# 01_-_POWER_SUPPLY.net
KiCad netlist of a schematic drawn in Altium Designer
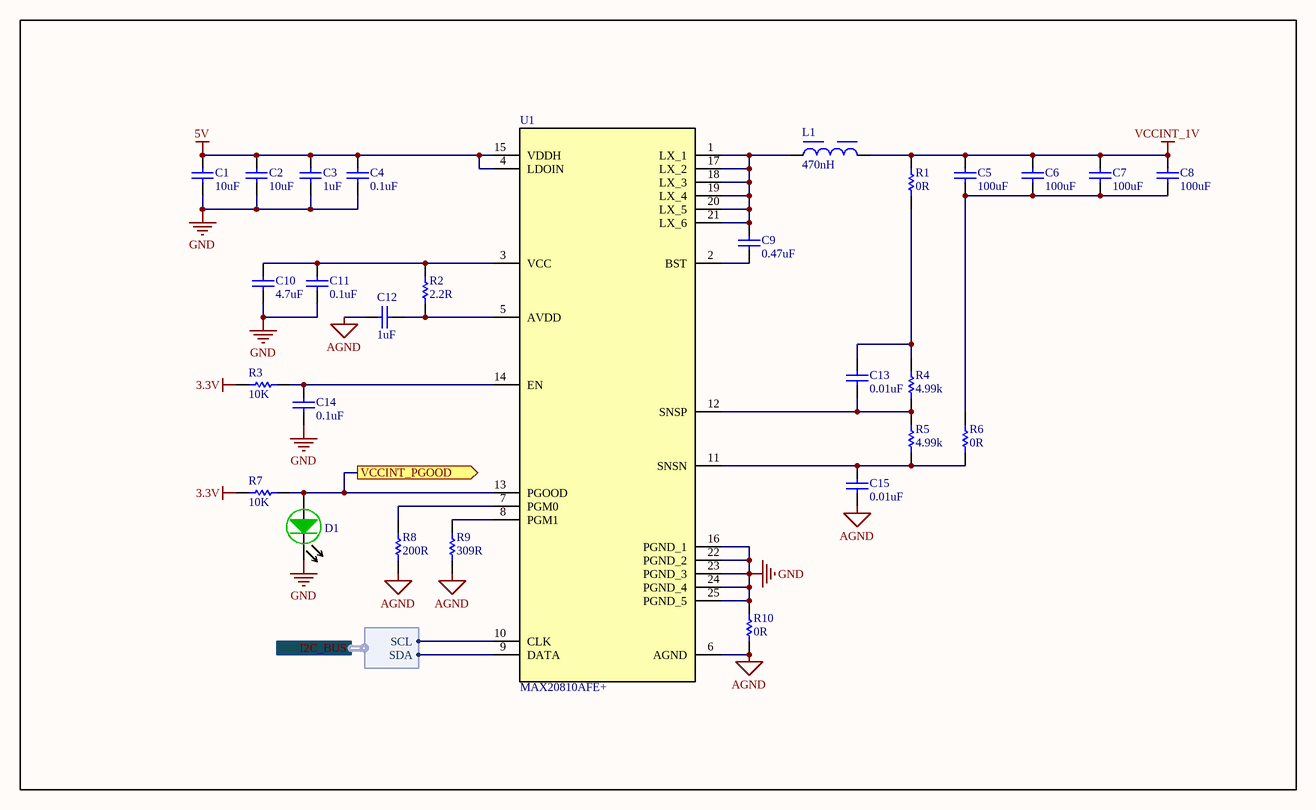
[diagram p0: 01 - POWER SUPPLY.SchDoc]

(export (version "E")
  (design (tool "Eeschema 10.0.6"))
  (components
    (comp (ref "C1")
      (value "10uF")
      (footprint "0603-C-R")
      (description "CAP SMD 0603 MLCC GERAL 10uF 10V ±10% X7R PN: GRM188Z71A106KA73D")
      (fields (field (name "VOLTAGE") "10V") (field (name "TOLERANCE") "10%"))
      (libsource (lib "Schlib") (part "CAP SMD 0603 10uF 10V ±10%"))
    )
    (comp (ref "C2")
      (value "10uF")
      (footprint "0603-C-R")
      (description "CAP SMD 0603 MLCC GERAL 10uF 10V ±10% X7R PN: GRM188Z71A106KA73D")
      (fields (field (name "VOLTAGE") "10V") (field (name "TOLERANCE") "10%"))
      (libsource (lib "Schlib") (part "CAP SMD 0603 10uF 10V ±10%"))
    )
    (comp (ref "C3")
      (value "1uF")
      (footprint "0402-C-R")
      (description "CAP SMD 0402 MLCC GERAL 1uF 25V ±10% 0402 X5R PN:GRM155R61E105KA12D MURATA")
      (fields (field (name "VOLTAGE") "25V") (field (name "TOLERANCE") "10%"))
      (libsource (lib "Schlib") (part "CAP SMD 0402 1uF 25V ±10%"))
    )
    (comp (ref "C4")
      (value "GRM155R71C104KA88J")
      (footprint "0402-C-R")
      (description "0.1 µF ±10% 16V Ceramic Capacitor X7R 0402 (1005 Metric)\r\nPN: GRM155R71C104KA88J")
      (fields (field (name "CAPACITANCE") "0.1uF"))
      (libsource (lib "Schlib") (part "CAP CER 0.1UF 16V X7R 0402"))
    )
    (comp (ref "C5")
      (value "100uF")
      (footprint "1210-C-R")
      (description "CAP SMD 1210 MLCC GERAL 100uF 6.3V ±20% X7S PN: GRM31CD80J107MEA8K")
      (fields (field (name "VOLTAGE") "6.3V") (field (name "TOLERANCE") "20%"))
      (libsource (lib "Schlib") (part "CAP SMD 1210 100uF 6.3V X7S ±20%"))
    )
    (comp (ref "C6")
      (value "100uF")
      (footprint "1210-C-R")
      (description "CAP SMD 1210 MLCC GERAL 100uF 6.3V ±20% X7S PN: GRM31CD80J107MEA8K")
      (fields (field (name "VOLTAGE") "6.3V") (field (name "TOLERANCE") "20%"))
      (libsource (lib "Schlib") (part "CAP SMD 1210 100uF 6.3V X7S ±20%"))
    )
    (comp (ref "C7")
      (value "100uF")
      (footprint "1210-C-R")
      (description "CAP SMD 1210 MLCC GERAL 100uF 6.3V ±20% X7S PN: GRM31CD80J107MEA8K")
      (fields (field (name "VOLTAGE") "6.3V") (field (name "TOLERANCE") "20%"))
      (libsource (lib "Schlib") (part "CAP SMD 1210 100uF 6.3V X7S ±20%"))
    )
    (comp (ref "C8")
      (value "100uF")
      (footprint "1210-C-R")
      (description "CAP SMD 1210 MLCC GERAL 100uF 6.3V ±20% X7S PN: GRM31CD80J107MEA8K")
      (fields (field (name "VOLTAGE") "6.3V") (field (name "TOLERANCE") "20%"))
      (libsource (lib "Schlib") (part "CAP SMD 1210 100uF 6.3V X7S ±20%"))
    )
    (comp (ref "C9")
      (value "CGA2B1X7S1C474K050BC")
      (footprint "0402-C-R")
      (description "0.1 µF ±10% 16V Ceramic Capacitor X7R 0402 (1005 Metric)\r\nPN: CGA2B1X7S1C474K050BC")
      (fields (field (name "CAPACITANCE") "0.47uF"))
      (libsource (lib "Schlib") (part "CAP CER 0.47UF 16V X7S 0402"))
    )
    (comp (ref "C10")
      (value "4.7uF")
      (footprint "0402-C-R")
      (description "CAP SMD 0402 MLCC GERAL 4.7uF 25V ±20% 0402 X5s PN: GRM155D81C475ME15J MURATA")
      (fields (field (name "VOLTAGE") "25V") (field (name "TOLERANCE") "20%"))
      (libsource (lib "Schlib") (part "CAP CER 4.7UF 25V X5R 0402"))
    )
    (comp (ref "C11")
      (value "GRM155R71C104KA88J")
      (footprint "0402-C-R")
      (description "0.1 µF ±10% 16V Ceramic Capacitor X7R 0402 (1005 Metric)\r\nPN: GRM155R71C104KA88J")
      (fields (field (name "CAPACITANCE") "0.1uF"))
      (libsource (lib "Schlib") (part "CAP CER 0.1UF 16V X7R 0402"))
    )
    (comp (ref "C12")
      (value "1uF")
      (footprint "0402-C-R")
      (description "1 µF ±10% 6.3V Ceramic Capacitor X5R 0402 (1005 Metric)")
      (fields (field (name "VOLTAGE") "6.3V") (field (name "TOLERANCE") "10%"))
      (libsource (lib "Schlib") (part "CAP CER 1UF 6.3V X5R 0402"))
    )
    (comp (ref "C13")
      (value "0.01uF")
      (footprint "0402-C-R")
      (description "10000 pF ±10% 16V Ceramic Capacitor X7R 0402 (1005 Metric)")
      (fields (field (name "VOLTAGE") "16V") (field (name "TOLERANCE") "10%"))
      (libsource (lib "Schlib") (part "CAP CER 10000PF 16V X7R 0402"))
    )
    (comp (ref "C14")
      (value "GRM155R71C104KA88J")
      (footprint "0402-C-R")
      (description "0.1 µF ±10% 16V Ceramic Capacitor X7R 0402 (1005 Metric)\r\nPN: GRM155R71C104KA88J")
      (fields (field (name "CAPACITANCE") "0.1uF"))
      (libsource (lib "Schlib") (part "CAP CER 0.1UF 16V X7R 0402"))
    )
    (comp (ref "C15")
      (value "0.01uF")
      (footprint "0402-C-R")
      (description "10000 pF ±10% 16V Ceramic Capacitor X7R 0402 (1005 Metric)")
      (fields (field (name "VOLTAGE") "16V") (field (name "TOLERANCE") "10%"))
      (libsource (lib "Schlib") (part "CAP CER 10000PF 16V X7R 0402"))
    )
    (comp (ref "D1")
      (value "LNJ347W83RA")
      (footprint "LED_0402")
      (description "Green 572nm LED Indication - Discrete 1.95V 0402 (1005 Metric)")
      (libsource (lib "Schlib") (part "LED GREEN 0402 SMD"))
    )
    (comp (ref "L1")
      (value "470nH")
      (footprint "WE-HCI_1365")
      (description "FIXED IND 470NH 30A 0.67 MOHM PN: 744355147")
      (fields
        (field (name "MF") "{'manufacturer': u'~{W}xfcrth Elektronik'}")
        (field (name "Comment") "744355147")
      )
      (libsource (lib "Schlib") (part "IND 470NH 30A 0.67 MOHM"))
    )
    (comp (ref "R1")
      (value "0R")
      (footprint "0402-R-R")
      (description "RES SMD GERAL FILM 0R 0.063W ±1% 0402 7\" TAPE PN: RMCF0402ZT0R00 STACKPOLE")
      (fields (field (name "TOLERANCE") "1%") (field (name "POWER") "0.063W"))
      (libsource (lib "Schlib") (part "RES SMD 0402 0R 0.063W ±1%"))
    )
    (comp (ref "R2")
      (value "2.2R")
      (footprint "0402-R-R")
      (description "RES SMD GERAL FILM 2.2R 0.063W ±1% 0402 7\" TAPE PN: RC0402FR-072R2L")
      (fields (field (name "POWER") "0.063W") (field (name "TOLERANCE") "1%"))
      (libsource (lib "Schlib") (part "RES SMD 0402 2.2R 0.063W ±1%"))
    )
    (comp (ref "R3")
      (value "10K")
      (footprint "0402-R-R")
      (description "10 kOhms ±1% 0,063W, 1/16W Resistor de chip 0402 (métrico 1005) Resistente à umidade Filme grosso")
      (fields (field (name "POWER") "0.063W") (field (name "TOLERANCE") "1%"))
      (libsource (lib "Schlib") (part "RES 10K OHM 1% 1/16W 0402"))
    )
    (comp (ref "R4")
      (value "RMCF0402FT4K99")
      (footprint "0402-R-R")
      (description "4.99 kOhms ±0.1% 0.063W, 1/16W Chip Resistor 0402 (1005 Metric) Automotive AEC-Q200 Thin Film")
      (fields (field (name "TOLERANCE") "1%") (field (name "RESISTENCE") "4.99k"))
      (libsource (lib "Schlib") (part "RES SMD 4K99 OHM 1% 1/16W 0402"))
    )
    (comp (ref "R5")
      (value "RMCF0402FT4K99")
      (footprint "0402-R-R")
      (description "4.99 kOhms ±0.1% 0.063W, 1/16W Chip Resistor 0402 (1005 Metric) Automotive AEC-Q200 Thin Film")
      (fields (field (name "TOLERANCE") "1%") (field (name "RESISTENCE") "4.99k"))
      (libsource (lib "Schlib") (part "RES SMD 4K99 OHM 1% 1/16W 0402"))
    )
    (comp (ref "R6")
      (value "0R")
      (footprint "0402-R-R")
      (description "RES SMD GERAL FILM 0R 0.063W ±1% 0402 7\" TAPE PN: RMCF0402ZT0R00 STACKPOLE")
      (fields (field (name "TOLERANCE") "1%") (field (name "POWER") "0.063W"))
      (libsource (lib "Schlib") (part "RES SMD 0402 0R 0.063W ±1%"))
    )
    (comp (ref "R7")
      (value "10K")
      (footprint "0402-R-R")
      (description "10 kOhms ±1% 0,063W, 1/16W Resistor de chip 0402 (métrico 1005) Resistente à umidade Filme grosso")
      (fields (field (name "POWER") "0.063W") (field (name "TOLERANCE") "1%"))
      (libsource (lib "Schlib") (part "RES 10K OHM 1% 1/16W 0402"))
    )
    (comp (ref "R8")
      (value "200R")
      (footprint "0402-R-R")
      (description "RES SMD GERAL FILM 200R 0.063W ±1% 0402 7\" TAPE PN: CRCW0402200RFKED")
      (fields (field (name "POWER") "0.063W") (field (name "TOLERANCE") "1%"))
      (libsource (lib "Schlib") (part "RES SMD 0402 200R 0.063W ±1%"))
    )
    (comp (ref "R9")
      (value "309R")
      (footprint "0402-R-R")
      (description "RES SMD GERAL FILM 309R 0.063W ±1% 0402 7\" TAPE PN: RC0402FR-072R2L")
      (fields (field (name "POWER") "0.063W") (field (name "TOLERANCE") "1%"))
      (libsource (lib "Schlib") (part "RES SMD 0402 309R 0.063W ±1%"))
    )
    (comp (ref "R10")
      (value "0R")
      (footprint "0402-R-R")
      (description "RES SMD GERAL FILM 0R 0.063W ±1% 0402 7\" TAPE PN: RMCF0402ZT0R00 STACKPOLE")
      (fields (field (name "TOLERANCE") "1%") (field (name "POWER") "0.063W"))
      (libsource (lib "Schlib") (part "RES SMD 0402 0R 0.063W ±1%"))
    )
    (comp (ref "U1")
      (value "MAX20810AFE+")
      (footprint "SamacSys:MAX20810AFE")
      (description "10A")
      (fields (field (name "MOUSER PART NUMBER") "700-MAX20810AFE+") (field (name "PN") "MAX20810AFE+"))
      (libsource (lib "Schlib") (part "IC REG BUCK ADJ 10A 16FC2QFN"))
    )
  )
  (nets
    (net (code "2") (name "/SCL") (class "Default")
      (node (ref "U1") (pin "10") (pinfunction "CLK_10") (pintype "passive"))
    )
    (net (code "3") (name "/SDA") (class "Default")
      (node (ref "U1") (pin "9") (pinfunction "DATA_9") (pintype "passive"))
    )
    (net (code "4") (name "/VCCINT_PGOOD") (class "Default")
      (node (ref "D1") (pin "2") (pinfunction "A_2") (pintype "passive"))
      (node (ref "R7") (pin "2") (pinfunction "2_2") (pintype "passive"))
      (node (ref "U1") (pin "13") (pinfunction "PGOOD_13") (pintype "passive"))
    )
    (net (code "6") (name "3.3V") (class "Default")
      (node (ref "R3") (pin "2") (pinfunction "2_2") (pintype "passive"))
      (node (ref "R7") (pin "1") (pinfunction "1_1") (pintype "passive"))
    )
    (net (code "7") (name "5V") (class "Default")
      (node (ref "C1") (pin "2") (pinfunction "2_2") (pintype "passive"))
      (node (ref "C2") (pin "2") (pinfunction "2_2") (pintype "passive"))
      (node (ref "C3") (pin "2") (pinfunction "2_2") (pintype "passive"))
      (node (ref "C4") (pin "2") (pinfunction "2_2") (pintype "passive"))
      (node (ref "U1") (pin "15") (pinfunction "VDDH_15") (pintype "passive"))
      (node (ref "U1") (pin "4") (pinfunction "LDOIN_4") (pintype "passive"))
    )
    (net (code "8") (name "AGND") (class "Default")
      (node (ref "C12") (pin "2") (pinfunction "2_2") (pintype "passive"))
      (node (ref "C15") (pin "1") (pinfunction "1_1") (pintype "passive"))
      (node (ref "R10") (pin "1") (pinfunction "1_1") (pintype "passive"))
      (node (ref "R8") (pin "1") (pinfunction "1_1") (pintype "passive"))
      (node (ref "R9") (pin "1") (pinfunction "1_1") (pintype "passive"))
      (node (ref "U1") (pin "6") (pinfunction "AGND_6") (pintype "passive"))
    )
    (net (code "9") (name "GND") (class "Default")
      (node (ref "C1") (pin "1") (pinfunction "1_1") (pintype "passive"))
      (node (ref "C10") (pin "1") (pinfunction "1_1") (pintype "passive"))
      (node (ref "C11") (pin "1") (pinfunction "1_1") (pintype "passive"))
      (node (ref "C14") (pin "1") (pinfunction "1_1") (pintype "passive"))
      (node (ref "C2") (pin "1") (pinfunction "1_1") (pintype "passive"))
      (node (ref "C3") (pin "1") (pinfunction "1_1") (pintype "passive"))
      (node (ref "C4") (pin "1") (pinfunction "1_1") (pintype "passive"))
      (node (ref "D1") (pin "1") (pinfunction "K_1") (pintype "passive"))
      (node (ref "R10") (pin "2") (pinfunction "2_2") (pintype "passive"))
      (node (ref "U1") (pin "16") (pinfunction "PGND_1_16") (pintype "passive"))
      (node (ref "U1") (pin "22") (pinfunction "PGND_2_22") (pintype "passive"))
      (node (ref "U1") (pin "23") (pinfunction "PGND_3_23") (pintype "passive"))
      (node (ref "U1") (pin "24") (pinfunction "PGND_4_24") (pintype "passive"))
      (node (ref "U1") (pin "25") (pinfunction "PGND_5_25") (pintype "passive"))
    )
    (net (code "10") (name "Net-(C5-Pad1)") (class "Default")
      (node (ref "C5") (pin "1") (pinfunction "1_1") (pintype "passive"))
      (node (ref "C6") (pin "1") (pinfunction "1_1") (pintype "passive"))
      (node (ref "C7") (pin "1") (pinfunction "1_1") (pintype "passive"))
      (node (ref "C8") (pin "1") (pinfunction "1_1") (pintype "passive"))
      (node (ref "R6") (pin "1") (pinfunction "1_1") (pintype "passive"))
    )
    (net (code "11") (name "Net-(C13-Pad2)") (class "Default")
      (node (ref "C13") (pin "2") (pinfunction "2_2") (pintype "passive"))
      (node (ref "R1") (pin "2") (pinfunction "2_2") (pintype "passive"))
      (node (ref "R4") (pin "2") (pinfunction "2_2") (pintype "passive"))
    )
    (net (code "12") (name "Net-(U1-AVDD)") (class "Default")
      (node (ref "C12") (pin "1") (pinfunction "1_1") (pintype "passive"))
      (node (ref "R2") (pin "1") (pinfunction "1_1") (pintype "passive"))
      (node (ref "U1") (pin "5") (pinfunction "AVDD_5") (pintype "passive"))
    )
    (net (code "13") (name "Net-(U1-BST)") (class "Default")
      (node (ref "C9") (pin "1") (pinfunction "1_1") (pintype "passive"))
      (node (ref "U1") (pin "2") (pinfunction "BST_2") (pintype "passive"))
    )
    (net (code "14") (name "Net-(U1-EN)") (class "Default")
      (node (ref "C14") (pin "2") (pinfunction "2_2") (pintype "passive"))
      (node (ref "R3") (pin "1") (pinfunction "1_1") (pintype "passive"))
      (node (ref "U1") (pin "14") (pinfunction "EN_14") (pintype "passive"))
    )
    (net (code "15") (name "Net-(U1-LX_1)") (class "Default")
      (node (ref "C9") (pin "2") (pinfunction "2_2") (pintype "passive"))
      (node (ref "L1") (pin "1") (pinfunction "1_1") (pintype "passive"))
      (node (ref "U1") (pin "1") (pinfunction "LX_1_1") (pintype "passive"))
      (node (ref "U1") (pin "17") (pinfunction "LX_2_17") (pintype "passive"))
      (node (ref "U1") (pin "18") (pinfunction "LX_3_18") (pintype "passive"))
      (node (ref "U1") (pin "19") (pinfunction "LX_4_19") (pintype "passive"))
      (node (ref "U1") (pin "20") (pinfunction "LX_5_20") (pintype "passive"))
      (node (ref "U1") (pin "21") (pinfunction "LX_6_21") (pintype "passive"))
    )
    (net (code "16") (name "Net-(U1-PGM0)") (class "Default")
      (node (ref "R8") (pin "2") (pinfunction "2_2") (pintype "passive"))
      (node (ref "U1") (pin "7") (pinfunction "PGM0_7") (pintype "passive"))
    )
    (net (code "17") (name "Net-(U1-PGM1)") (class "Default")
      (node (ref "R9") (pin "2") (pinfunction "2_2") (pintype "passive"))
      (node (ref "U1") (pin "8") (pinfunction "PGM1_8") (pintype "passive"))
    )
    (net (code "18") (name "Net-(U1-SNSN)") (class "Default")
      (node (ref "C15") (pin "2") (pinfunction "2_2") (pintype "passive"))
      (node (ref "R5") (pin "1") (pinfunction "1_1") (pintype "passive"))
      (node (ref "R6") (pin "2") (pinfunction "2_2") (pintype "passive"))
      (node (ref "U1") (pin "11") (pinfunction "SNSN_11") (pintype "passive"))
    )
    (net (code "19") (name "Net-(U1-SNSP)") (class "Default")
      (node (ref "C13") (pin "1") (pinfunction "1_1") (pintype "passive"))
      (node (ref "R4") (pin "1") (pinfunction "1_1") (pintype "passive"))
      (node (ref "R5") (pin "2") (pinfunction "2_2") (pintype "passive"))
      (node (ref "U1") (pin "12") (pinfunction "SNSP_12") (pintype "passive"))
    )
    (net (code "20") (name "Net-(U1-VCC)") (class "Default")
      (node (ref "C10") (pin "2") (pinfunction "2_2") (pintype "passive"))
      (node (ref "C11") (pin "2") (pinfunction "2_2") (pintype "passive"))
      (node (ref "R2") (pin "2") (pinfunction "2_2") (pintype "passive"))
      (node (ref "U1") (pin "3") (pinfunction "VCC_3") (pintype "passive"))
    )
    (net (code "21") (name "VCCINT_1V") (class "Default")
      (node (ref "C5") (pin "2") (pinfunction "2_2") (pintype "passive"))
      (node (ref "C6") (pin "2") (pinfunction "2_2") (pintype "passive"))
      (node (ref "C7") (pin "2") (pinfunction "2_2") (pintype "passive"))
      (node (ref "C8") (pin "2") (pinfunction "2_2") (pintype "passive"))
      (node (ref "L1") (pin "2") (pinfunction "2_2") (pintype "passive"))
      (node (ref "R1") (pin "1") (pinfunction "1_1") (pintype "passive"))
    )
  )
)
